# board.net
KiCad netlist of a schematic drawn in EAGLE
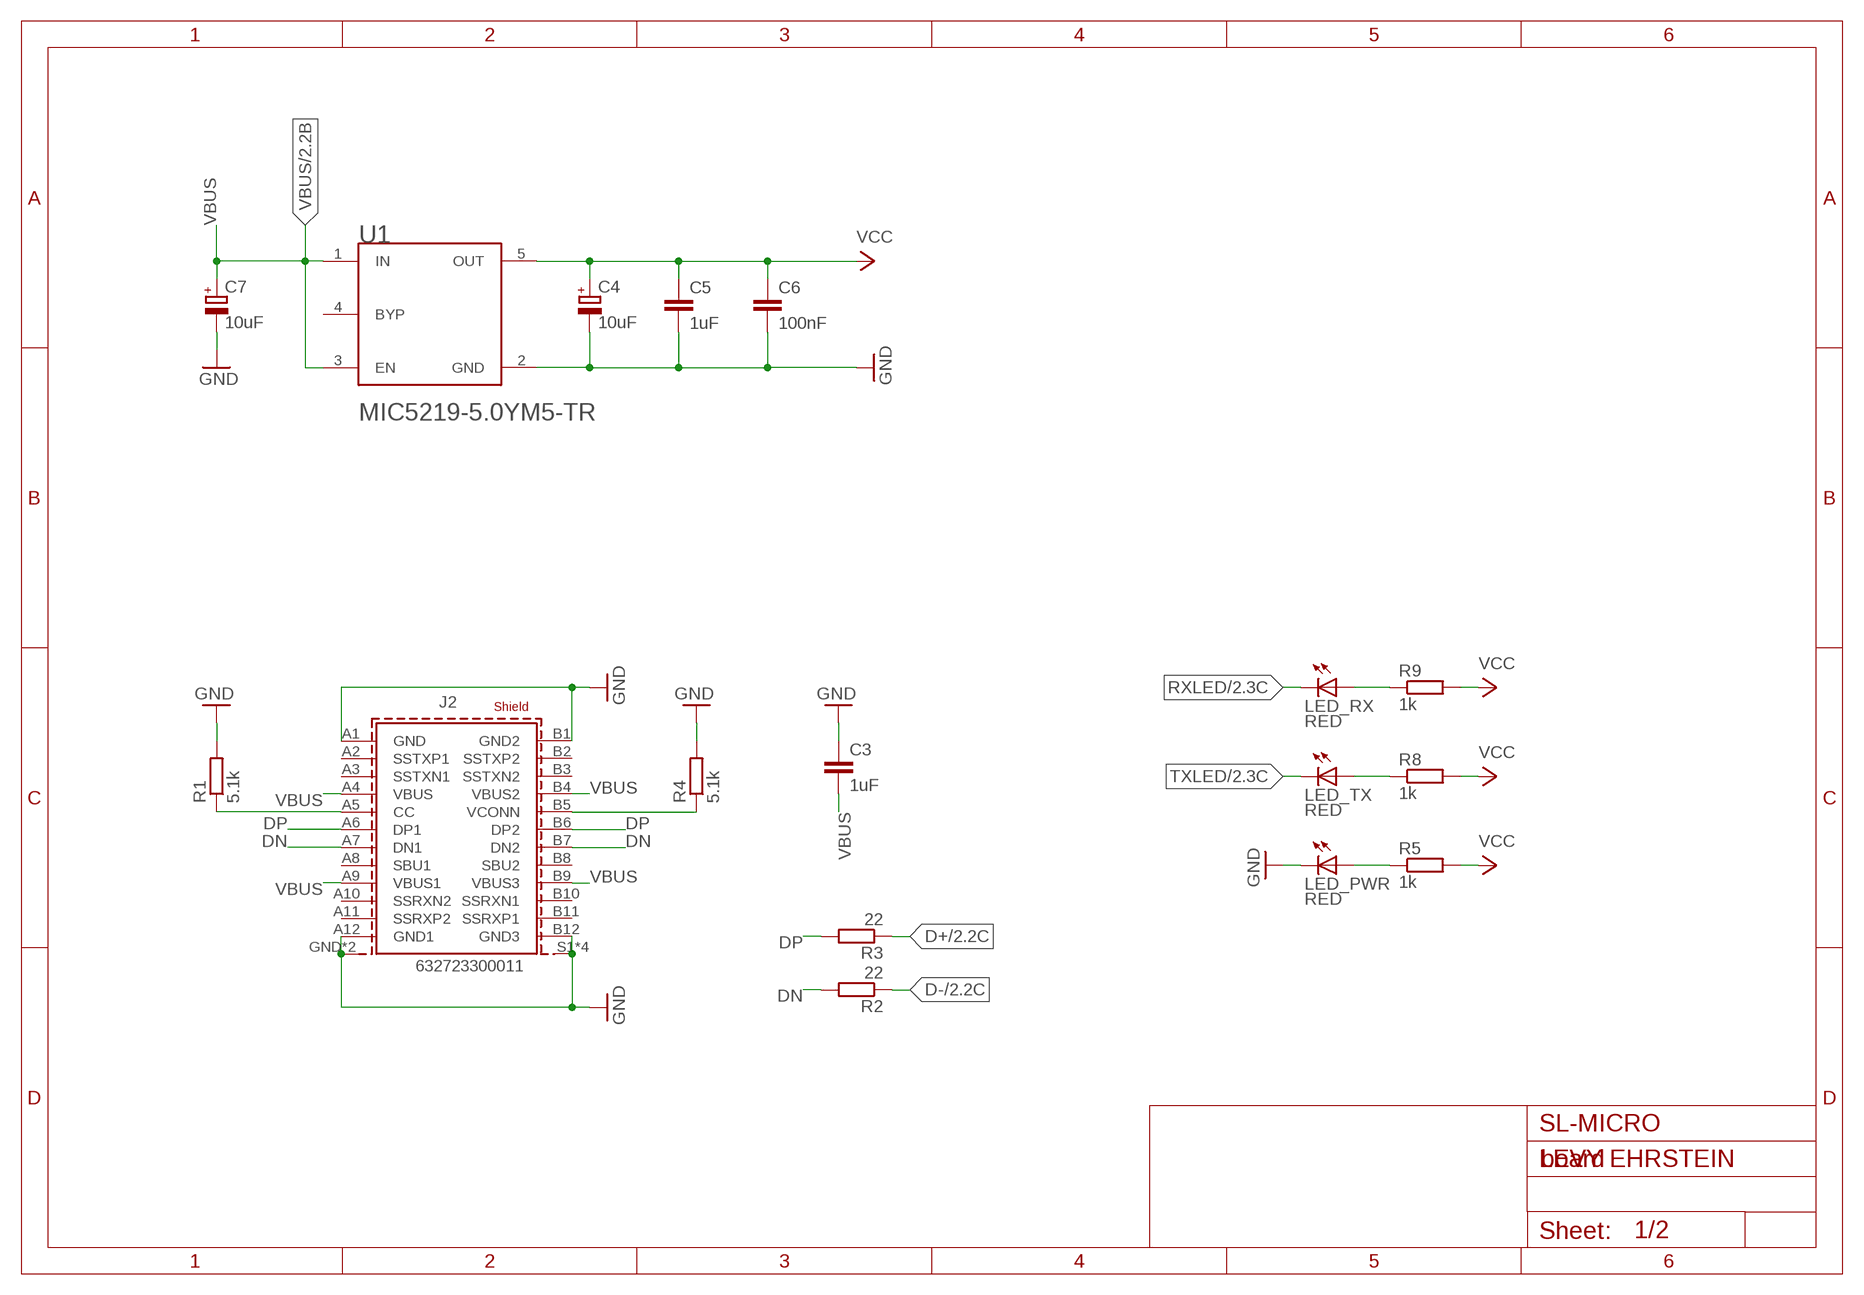
[diagram p0: schematic, sheet 1]
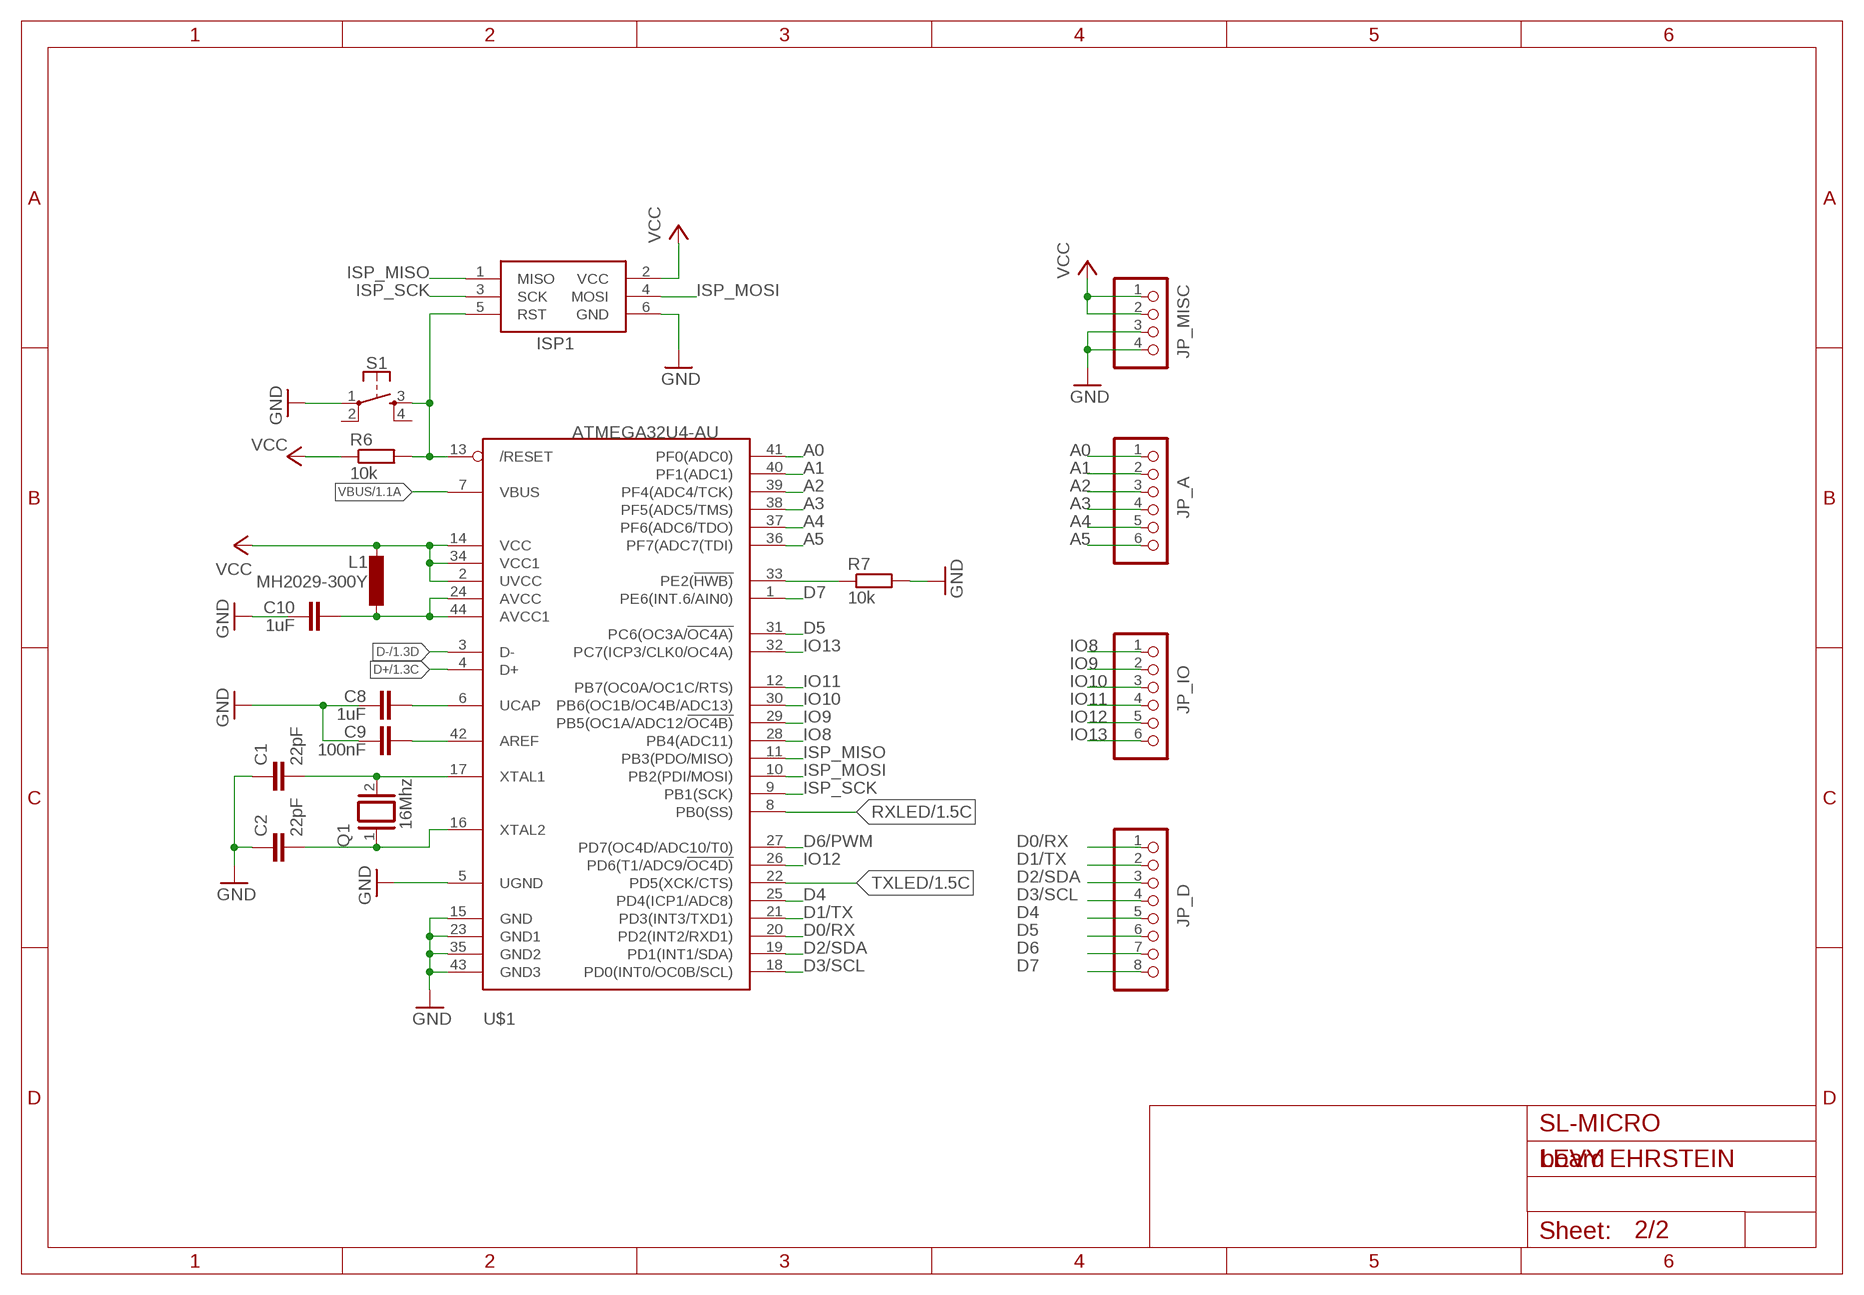
[diagram p1: schematic, sheet 2]

(export (version "E")
  (design (tool "Eeschema 10.0.6"))
  (components
    (comp (ref "C1")
      (value "22pF")
      (footprint "eagle-import:C0805")
      (libsource (lib "eagle-import") (part "C-EUC0805"))
    )
    (comp (ref "C2")
      (value "22pF")
      (footprint "eagle-import:C0805")
      (libsource (lib "eagle-import") (part "C-EUC0805"))
    )
    (comp (ref "C8")
      (value "1uF")
      (footprint "eagle-import:C0805")
      (libsource (lib "eagle-import") (part "C-EUC0805"))
    )
    (comp (ref "C9")
      (value "100nF")
      (footprint "eagle-import:C0805")
      (libsource (lib "eagle-import") (part "C-EUC0805"))
    )
    (comp (ref "C10")
      (value "1uF")
      (footprint "eagle-import:C0805")
      (libsource (lib "eagle-import") (part "C-EUC0805"))
    )
    (comp (ref "ISP1")
      (value "AVRISP-6")
      (footprint "eagle-import:AVRISP")
      (libsource (lib "eagle-import") (part "AVRISP-6"))
    )
    (comp (ref "JP_A")
      (value "PINHD-1X6")
      (footprint "eagle-import:1X06")
      (libsource (lib "eagle-import") (part "PINHD-1X6"))
    )
    (comp (ref "JP_D")
      (value "PINHD-1X8")
      (footprint "eagle-import:1X08")
      (libsource (lib "eagle-import") (part "PINHD-1X8"))
    )
    (comp (ref "JP_IO")
      (value "PINHD-1X6")
      (footprint "eagle-import:1X06")
      (libsource (lib "eagle-import") (part "PINHD-1X6"))
    )
    (comp (ref "JP_MISC")
      (value "PINHD-1X4")
      (footprint "eagle-import:1X04")
      (libsource (lib "eagle-import") (part "PINHD-1X4"))
    )
    (comp (ref "L1")
      (value "MH2029-300Y")
      (footprint "eagle-import:L2012C")
      (libsource (lib "eagle-import") (part "L-EUL2012C"))
    )
    (comp (ref "Q1")
      (value "16Mhz")
      (footprint "eagle-import:QS")
      (libsource (lib "eagle-import") (part "XTAL/S"))
    )
    (comp (ref "R6")
      (value "10k")
      (footprint "eagle-import:R0805")
      (libsource (lib "eagle-import") (part "R-EU_R0805"))
    )
    (comp (ref "R7")
      (value "10k")
      (footprint "eagle-import:R0805")
      (libsource (lib "eagle-import") (part "R-EU_R0805"))
    )
    (comp (ref "S1")
      (value "MOMENTARY-SWITCH-SPST-2-SMD-4.6X2.8MM")
      (footprint "eagle-import:TACTILE_SWITCH_SMD_4.6X2.8MM")
      (libsource (lib "eagle-import") (part "MOMENTARY-SWITCH-SPST-2-SMD-4.6X2.8MM"))
    )
    (comp (ref "U$1")
      (value "ATMEGA32U4-AU")
      (footprint "eagle-import:TQFP44")
      (libsource (lib "eagle-import") (part "ATMEGA32U4-AU"))
    )
    (comp (ref "C3")
      (value "1uF")
      (footprint "eagle-import:C0805")
      (libsource (lib "eagle-import") (part "C-EUC0805"))
    )
    (comp (ref "C4")
      (value "10uF")
      (footprint "eagle-import:SMC_B")
      (libsource (lib "eagle-import") (part "CPOL-EUSMCB"))
    )
    (comp (ref "C5")
      (value "1uF")
      (footprint "eagle-import:C0805")
      (libsource (lib "eagle-import") (part "C-EUC0805"))
    )
    (comp (ref "C6")
      (value "100nF")
      (footprint "eagle-import:C0805")
      (libsource (lib "eagle-import") (part "C-EUC0805"))
    )
    (comp (ref "C7")
      (value "10uF")
      (footprint "eagle-import:SMC_B")
      (libsource (lib "eagle-import") (part "CPOL-EUSMCB"))
    )
    (comp (ref "J2")
      (value "632723300011")
      (footprint "eagle-import:632723300011")
      (libsource (lib "eagle-import") (part "632723300011"))
    )
    (comp (ref "LED_PWR")
      (value "RED")
      (footprint "eagle-import:CHIP-LED0805")
      (libsource (lib "eagle-import") (part "LEDCHIP-LED0805"))
    )
    (comp (ref "LED_RX")
      (value "RED")
      (footprint "eagle-import:CHIP-LED0805")
      (libsource (lib "eagle-import") (part "LEDCHIP-LED0805"))
    )
    (comp (ref "LED_TX")
      (value "RED")
      (footprint "eagle-import:CHIP-LED0805")
      (libsource (lib "eagle-import") (part "LEDCHIP-LED0805"))
    )
    (comp (ref "R1")
      (value "5.1k")
      (footprint "eagle-import:R0805")
      (libsource (lib "eagle-import") (part "R-EU_R0805"))
    )
    (comp (ref "R2")
      (value "22")
      (footprint "eagle-import:R0805")
      (libsource (lib "eagle-import") (part "R-EU_R0805"))
    )
    (comp (ref "R3")
      (value "22")
      (footprint "eagle-import:R0805")
      (libsource (lib "eagle-import") (part "R-EU_R0805"))
    )
    (comp (ref "R4")
      (value "5.1k")
      (footprint "eagle-import:R0805")
      (libsource (lib "eagle-import") (part "R-EU_R0805"))
    )
    (comp (ref "R5")
      (value "1k")
      (footprint "eagle-import:R0805")
      (libsource (lib "eagle-import") (part "R-EU_R0805"))
    )
    (comp (ref "R8")
      (value "1k")
      (footprint "eagle-import:R0805")
      (libsource (lib "eagle-import") (part "R-EU_R0805"))
    )
    (comp (ref "R9")
      (value "1k")
      (footprint "eagle-import:R0805")
      (libsource (lib "eagle-import") (part "R-EU_R0805"))
    )
    (comp (ref "U1")
      (value "MICROCHIP_TECHNOLOGY_MIC5219-5_0YM5-TRMICROCHIP_TECHNOLOGY_MIC5219-5_0YM5-TR_0_0")
      (footprint "eagle-import:MICROCHIP_TECHNOLOGY_MIC5219-5_0YM5-TR_0")
      (fields
        (field (name "DIGIKEY_PART_NUMBER") "576-2770-1-ND")
        (field (name "MF") "Microchip Technology")
        (field (name "MOUSER_PART_NUMBER") "998-MIC5219-5.0YM5TR")
      )
      (libsource (lib "eagle-import") (part "MICROCHIP_TECHNOLOGY_MIC5219-5_0YM5-TRMICROCHIP_TECHNOLOGY_MIC5219-5_0YM5-TR_0_0"))
    )
  )
  (nets
    (net (code "1") (name "A0") (class "Default")
      (node (ref "JP_A") (pin "1") (pinfunction "1_1") (pintype "passive"))
      (node (ref "U$1") (pin "41") (pinfunction "PF0(ADC0)_41") (pintype "bidirectional"))
    )
    (net (code "2") (name "A1") (class "Default")
      (node (ref "JP_A") (pin "2") (pinfunction "2_2") (pintype "passive"))
      (node (ref "U$1") (pin "40") (pinfunction "PF1(ADC1)_40") (pintype "bidirectional"))
    )
    (net (code "3") (name "A2") (class "Default")
      (node (ref "JP_A") (pin "3") (pinfunction "3_3") (pintype "passive"))
      (node (ref "U$1") (pin "39") (pinfunction "PF4(ADC4/TCK)_39") (pintype "bidirectional"))
    )
    (net (code "4") (name "A3") (class "Default")
      (node (ref "JP_A") (pin "4") (pinfunction "4_4") (pintype "passive"))
      (node (ref "U$1") (pin "38") (pinfunction "PF5(ADC5/TMS)_38") (pintype "bidirectional"))
    )
    (net (code "5") (name "A4") (class "Default")
      (node (ref "JP_A") (pin "5") (pinfunction "5_5") (pintype "passive"))
      (node (ref "U$1") (pin "37") (pinfunction "PF6(ADC6/TDO)_37") (pintype "bidirectional"))
    )
    (net (code "6") (name "A5") (class "Default")
      (node (ref "JP_A") (pin "6") (pinfunction "6_6") (pintype "passive"))
      (node (ref "U$1") (pin "36") (pinfunction "PF7(ADC7(TDI)_36") (pintype "bidirectional"))
    )
    (net (code "7") (name "D+") (class "Default")
      (node (ref "R3") (pin "1") (pinfunction "1_1") (pintype "passive"))
      (node (ref "U$1") (pin "4") (pinfunction "D+_4") (pintype "bidirectional"))
    )
    (net (code "8") (name "D-") (class "Default")
      (node (ref "R2") (pin "1") (pinfunction "1_1") (pintype "passive"))
      (node (ref "U$1") (pin "3") (pinfunction "D-_3") (pintype "bidirectional"))
    )
    (net (code "9") (name "D0{slash}RX") (class "Default")
      (node (ref "JP_D") (pin "1") (pinfunction "1_1") (pintype "passive"))
      (node (ref "U$1") (pin "20") (pinfunction "PD2(INT2/RXD1)_20") (pintype "bidirectional"))
    )
    (net (code "10") (name "D1{slash}TX") (class "Default")
      (node (ref "JP_D") (pin "2") (pinfunction "2_2") (pintype "passive"))
      (node (ref "U$1") (pin "21") (pinfunction "PD3(INT3/TXD1)_21") (pintype "bidirectional"))
    )
    (net (code "11") (name "D2{slash}SDA") (class "Default")
      (node (ref "JP_D") (pin "3") (pinfunction "3_3") (pintype "passive"))
      (node (ref "U$1") (pin "19") (pinfunction "PD1(INT1/SDA)_19") (pintype "bidirectional"))
    )
    (net (code "12") (name "D3{slash}SCL") (class "Default")
      (node (ref "JP_D") (pin "4") (pinfunction "4_4") (pintype "passive"))
      (node (ref "U$1") (pin "18") (pinfunction "PD0(INT0/OC0B/SCL)_18") (pintype "bidirectional"))
    )
    (net (code "13") (name "D4") (class "Default")
      (node (ref "JP_D") (pin "5") (pinfunction "5_5") (pintype "passive"))
      (node (ref "U$1") (pin "25") (pinfunction "PD4(ICP1/ADC8)_25") (pintype "bidirectional"))
    )
    (net (code "14") (name "D5") (class "Default")
      (node (ref "JP_D") (pin "6") (pinfunction "6_6") (pintype "passive"))
      (node (ref "U$1") (pin "31") (pinfunction "PC6(OC3A/~{OC4A})_31") (pintype "bidirectional"))
    )
    (net (code "15") (name "D6") (class "Default")
      (node (ref "JP_D") (pin "7") (pinfunction "7_7") (pintype "passive"))
    )
    (net (code "16") (name "D6{slash}PWM") (class "Default")
      (node (ref "U$1") (pin "27") (pinfunction "PD7(OC4D/ADC10/T0)_27") (pintype "bidirectional"))
    )
    (net (code "17") (name "D7") (class "Default")
      (node (ref "JP_D") (pin "8") (pinfunction "8_8") (pintype "passive"))
      (node (ref "U$1") (pin "1") (pinfunction "PE6(INT.6/AIN0)_1") (pintype "bidirectional"))
    )
    (net (code "18") (name "DN") (class "Default")
      (node (ref "J2") (pin "A7") (pinfunction "DN1_A7") (pintype "bidirectional"))
      (node (ref "J2") (pin "B7") (pinfunction "DN2_B7") (pintype "bidirectional"))
      (node (ref "R2") (pin "2") (pinfunction "2_2") (pintype "passive"))
    )
    (net (code "19") (name "DP") (class "Default")
      (node (ref "J2") (pin "A6") (pinfunction "DP1_A6") (pintype "bidirectional"))
      (node (ref "J2") (pin "B6") (pinfunction "DP2_B6") (pintype "bidirectional"))
      (node (ref "R3") (pin "2") (pinfunction "2_2") (pintype "passive"))
    )
    (net (code "20") (name "GND") (class "Default")
      (node (ref "C1") (pin "1") (pinfunction "1_1") (pintype "passive"))
      (node (ref "C10") (pin "1") (pinfunction "1_1") (pintype "passive"))
      (node (ref "C2") (pin "1") (pinfunction "1_1") (pintype "passive"))
      (node (ref "C3") (pin "1") (pinfunction "1_1") (pintype "passive"))
      (node (ref "C4") (pin "-") (pinfunction "-_-") (pintype "passive"))
      (node (ref "C5") (pin "2") (pinfunction "2_2") (pintype "passive"))
      (node (ref "C6") (pin "2") (pinfunction "2_2") (pintype "passive"))
      (node (ref "C7") (pin "-") (pinfunction "-_-") (pintype "passive"))
      (node (ref "C8") (pin "1") (pinfunction "1_1") (pintype "passive"))
      (node (ref "C9") (pin "1") (pinfunction "1_1") (pintype "passive"))
      (node (ref "ISP1") (pin "6") (pinfunction "GND_6") (pintype "power_in"))
      (node (ref "J2") (pin "A1") (pinfunction "GND_A1") (pintype "bidirectional"))
      (node (ref "J2") (pin "A12") (pinfunction "GND1_A12") (pintype "bidirectional"))
      (node (ref "J2") (pin "B1") (pinfunction "GND2_B1") (pintype "bidirectional"))
      (node (ref "J2") (pin "B12") (pinfunction "GND3_B12") (pintype "bidirectional"))
      (node (ref "J2") (pin "GND") (pinfunction "SHIELD_GND") (pintype "bidirectional"))
      (node (ref "J2") (pin "GND1") (pinfunction "SHIELD_GND1") (pintype "bidirectional"))
      (node (ref "J2") (pin "S1") (pinfunction "SHIELD1_S1") (pintype "bidirectional"))
      (node (ref "J2") (pin "S2") (pinfunction "SHIELD1_S2") (pintype "bidirectional"))
      (node (ref "J2") (pin "S3") (pinfunction "SHIELD1_S3") (pintype "bidirectional"))
      (node (ref "J2") (pin "S4") (pinfunction "SHIELD1_S4") (pintype "bidirectional"))
      (node (ref "JP_MISC") (pin "3") (pinfunction "3_3") (pintype "passive"))
      (node (ref "JP_MISC") (pin "4") (pinfunction "4_4") (pintype "passive"))
      (node (ref "LED_PWR") (pin "C") (pinfunction "C_C") (pintype "passive"))
      (node (ref "R1") (pin "2") (pinfunction "2_2") (pintype "passive"))
      (node (ref "R4") (pin "2") (pinfunction "2_2") (pintype "passive"))
      (node (ref "R7") (pin "2") (pinfunction "2_2") (pintype "passive"))
      (node (ref "S1") (pin "1") (pinfunction "1_1") (pintype "passive"))
      (node (ref "U$1") (pin "15") (pinfunction "GND_15") (pintype "bidirectional"))
      (node (ref "U$1") (pin "23") (pinfunction "GND1_23") (pintype "bidirectional"))
      (node (ref "U$1") (pin "35") (pinfunction "GND2_35") (pintype "bidirectional"))
      (node (ref "U$1") (pin "43") (pinfunction "GND3_43") (pintype "bidirectional"))
      (node (ref "U$1") (pin "5") (pinfunction "UGND_5") (pintype "bidirectional"))
      (node (ref "U1") (pin "2") (pinfunction "GND_2") (pintype "power_in"))
    )
    (net (code "21") (name "IO8") (class "Default")
      (node (ref "JP_IO") (pin "1") (pinfunction "1_1") (pintype "passive"))
      (node (ref "U$1") (pin "28") (pinfunction "PB4(ADC11)_28") (pintype "bidirectional"))
    )
    (net (code "22") (name "IO9") (class "Default")
      (node (ref "JP_IO") (pin "2") (pinfunction "2_2") (pintype "passive"))
      (node (ref "U$1") (pin "29") (pinfunction "PB5(OC1A/ADC12/~{OC4B})_29") (pintype "bidirectional"))
    )
    (net (code "23") (name "IO10") (class "Default")
      (node (ref "JP_IO") (pin "3") (pinfunction "3_3") (pintype "passive"))
      (node (ref "U$1") (pin "30") (pinfunction "PB6(OC1B/OC4B/ADC13)_30") (pintype "bidirectional"))
    )
    (net (code "24") (name "IO11") (class "Default")
      (node (ref "JP_IO") (pin "4") (pinfunction "4_4") (pintype "passive"))
      (node (ref "U$1") (pin "12") (pinfunction "PB7(OC0A/OC1C/RTS)_12") (pintype "bidirectional"))
    )
    (net (code "25") (name "IO12") (class "Default")
      (node (ref "JP_IO") (pin "5") (pinfunction "5_5") (pintype "passive"))
      (node (ref "U$1") (pin "26") (pinfunction "PD6(T1/ADC9/~{OC4D})_26") (pintype "bidirectional"))
    )
    (net (code "26") (name "IO13") (class "Default")
      (node (ref "JP_IO") (pin "6") (pinfunction "6_6") (pintype "passive"))
      (node (ref "U$1") (pin "32") (pinfunction "PC7(ICP3/CLK0/OC4A)_32") (pintype "bidirectional"))
    )
    (net (code "27") (name "ISP_MISO") (class "Default")
      (node (ref "ISP1") (pin "1") (pinfunction "MISO_1") (pintype "input"))
      (node (ref "U$1") (pin "11") (pinfunction "PB3(PDO/MISO)_11") (pintype "bidirectional"))
    )
    (net (code "28") (name "ISP_MOSI") (class "Default")
      (node (ref "ISP1") (pin "4") (pinfunction "MOSI_4") (pintype "output"))
      (node (ref "U$1") (pin "10") (pinfunction "PB2(PDI/MOSI)_10") (pintype "bidirectional"))
    )
    (net (code "29") (name "ISP_SCK") (class "Default")
      (node (ref "ISP1") (pin "3") (pinfunction "SCK_3") (pintype "output"))
      (node (ref "U$1") (pin "9") (pinfunction "PB1(SCK)_9") (pintype "bidirectional"))
    )
    (net (code "30") (name "Net-(ISP1-RST)") (class "Default")
      (node (ref "ISP1") (pin "5") (pinfunction "RST_5") (pintype "output"))
      (node (ref "R6") (pin "2") (pinfunction "2_2") (pintype "passive"))
      (node (ref "S1") (pin "3") (pinfunction "3_3") (pintype "passive"))
      (node (ref "U$1") (pin "13") (pinfunction "/RESET_13") (pintype "bidirectional"))
    )
    (net (code "31") (name "Net-(J2-CC)") (class "Default")
      (node (ref "J2") (pin "A5") (pinfunction "CC_A5") (pintype "bidirectional"))
      (node (ref "R1") (pin "1") (pinfunction "1_1") (pintype "passive"))
    )
    (net (code "32") (name "Net-(J2-VCONN)") (class "Default")
      (node (ref "J2") (pin "B5") (pinfunction "VCONN_B5") (pintype "bidirectional"))
      (node (ref "R4") (pin "1") (pinfunction "1_1") (pintype "passive"))
    )
    (net (code "33") (name "Net-(LED_PWR-PadA)") (class "Default")
      (node (ref "LED_PWR") (pin "A") (pinfunction "A_A") (pintype "passive"))
      (node (ref "R5") (pin "1") (pinfunction "1_1") (pintype "passive"))
    )
    (net (code "34") (name "Net-(LED_RX-PadA)") (class "Default")
      (node (ref "LED_RX") (pin "A") (pinfunction "A_A") (pintype "passive"))
      (node (ref "R9") (pin "1") (pinfunction "1_1") (pintype "passive"))
    )
    (net (code "35") (name "Net-(LED_TX-PadA)") (class "Default")
      (node (ref "LED_TX") (pin "A") (pinfunction "A_A") (pintype "passive"))
      (node (ref "R8") (pin "1") (pinfunction "1_1") (pintype "passive"))
    )
    (net (code "36") (name "Net-(U$1-AREF)") (class "Default")
      (node (ref "C9") (pin "2") (pinfunction "2_2") (pintype "passive"))
      (node (ref "U$1") (pin "42") (pinfunction "AREF_42") (pintype "bidirectional"))
    )
    (net (code "37") (name "Net-(U$1-AVCC)") (class "Default")
      (node (ref "C10") (pin "2") (pinfunction "2_2") (pintype "passive"))
      (node (ref "L1") (pin "1") (pinfunction "1_1") (pintype "passive"))
      (node (ref "U$1") (pin "24") (pinfunction "AVCC_24") (pintype "bidirectional"))
      (node (ref "U$1") (pin "44") (pinfunction "AVCC1_44") (pintype "bidirectional"))
    )
    (net (code "38") (name "Net-(U$1-PE2(~{HWB}))") (class "Default")
      (node (ref "R7") (pin "1") (pinfunction "1_1") (pintype "passive"))
      (node (ref "U$1") (pin "33") (pinfunction "PE2(~{HWB})_33") (pintype "bidirectional"))
    )
    (net (code "39") (name "Net-(U$1-UCAP)") (class "Default")
      (node (ref "C8") (pin "2") (pinfunction "2_2") (pintype "passive"))
      (node (ref "U$1") (pin "6") (pinfunction "UCAP_6") (pintype "bidirectional"))
    )
    (net (code "40") (name "Net-(U$1-XTAL1)") (class "Default")
      (node (ref "C1") (pin "2") (pinfunction "2_2") (pintype "passive"))
      (node (ref "Q1") (pin "2") (pinfunction "2_2") (pintype "passive"))
      (node (ref "U$1") (pin "17") (pinfunction "XTAL1_17") (pintype "bidirectional"))
    )
    (net (code "41") (name "Net-(U$1-XTAL2)") (class "Default")
      (node (ref "C2") (pin "2") (pinfunction "2_2") (pintype "passive"))
      (node (ref "Q1") (pin "1") (pinfunction "1_1") (pintype "passive"))
      (node (ref "U$1") (pin "16") (pinfunction "XTAL2_16") (pintype "bidirectional"))
    )
    (net (code "42") (name "RXLED") (class "Default")
      (node (ref "LED_RX") (pin "C") (pinfunction "C_C") (pintype "passive"))
      (node (ref "U$1") (pin "8") (pinfunction "PB0(SS)_8") (pintype "bidirectional"))
    )
    (net (code "43") (name "TXLED") (class "Default")
      (node (ref "LED_TX") (pin "C") (pinfunction "C_C") (pintype "passive"))
      (node (ref "U$1") (pin "22") (pinfunction "PD5(XCK/CTS)_22") (pintype "bidirectional"))
    )
    (net (code "44") (name "VBUS") (class "Default")
      (node (ref "C3") (pin "2") (pinfunction "2_2") (pintype "passive"))
      (node (ref "C7") (pin "+") (pinfunction "+_+") (pintype "passive"))
      (node (ref "J2") (pin "A4") (pinfunction "VBUS_A4") (pintype "bidirectional"))
      (node (ref "J2") (pin "A9") (pinfunction "VBUS1_A9") (pintype "bidirectional"))
      (node (ref "J2") (pin "B4") (pinfunction "VBUS2_B4") (pintype "bidirectional"))
      (node (ref "J2") (pin "B9") (pinfunction "VBUS3_B9") (pintype "bidirectional"))
      (node (ref "U$1") (pin "7") (pinfunction "VBUS_7") (pintype "bidirectional"))
      (node (ref "U1") (pin "1") (pinfunction "IN_1") (pintype "power_in"))
      (node (ref "U1") (pin "3") (pinfunction "EN_3") (pintype "input"))
    )
    (net (code "45") (name "VCC") (class "Default")
      (node (ref "C4") (pin "+") (pinfunction "+_+") (pintype "passive"))
      (node (ref "C5") (pin "1") (pinfunction "1_1") (pintype "passive"))
      (node (ref "C6") (pin "1") (pinfunction "1_1") (pintype "passive"))
      (node (ref "ISP1") (pin "2") (pinfunction "VCC_2") (pintype "power_in"))
      (node (ref "JP_MISC") (pin "1") (pinfunction "1_1") (pintype "passive"))
      (node (ref "JP_MISC") (pin "2") (pinfunction "2_2") (pintype "passive"))
      (node (ref "L1") (pin "2") (pinfunction "2_2") (pintype "passive"))
      (node (ref "R5") (pin "2") (pinfunction "2_2") (pintype "passive"))
      (node (ref "R6") (pin "1") (pinfunction "1_1") (pintype "passive"))
      (node (ref "R8") (pin "2") (pinfunction "2_2") (pintype "passive"))
      (node (ref "R9") (pin "2") (pinfunction "2_2") (pintype "passive"))
      (node (ref "U$1") (pin "14") (pinfunction "VCC_14") (pintype "bidirectional"))
      (node (ref "U$1") (pin "2") (pinfunction "UVCC_2") (pintype "bidirectional"))
      (node (ref "U$1") (pin "34") (pinfunction "VCC1_34") (pintype "bidirectional"))
      (node (ref "U1") (pin "5") (pinfunction "OUT_5") (pintype "power_in"))
    )
    (net (code "46") (name "unconnected-(J2-SBU1-PadA8)") (class "Default")
      (node (ref "J2") (pin "A8") (pinfunction "SBU1_A8") (pintype "bidirectional"))
    )
    (net (code "47") (name "unconnected-(J2-SBU2-PadB8)") (class "Default")
      (node (ref "J2") (pin "B8") (pinfunction "SBU2_B8") (pintype "bidirectional"))
    )
    (net (code "48") (name "unconnected-(J2-SSRXN1-PadB10)") (class "Default")
      (node (ref "J2") (pin "B10") (pinfunction "SSRXN1_B10") (pintype "bidirectional"))
    )
    (net (code "49") (name "unconnected-(J2-SSRXN2-PadA10)") (class "Default")
      (node (ref "J2") (pin "A10") (pinfunction "SSRXN2_A10") (pintype "bidirectional"))
    )
    (net (code "50") (name "unconnected-(J2-SSRXP1-PadB11)") (class "Default")
      (node (ref "J2") (pin "B11") (pinfunction "SSRXP1_B11") (pintype "bidirectional"))
    )
    (net (code "51") (name "unconnected-(J2-SSRXP2-PadA11)") (class "Default")
      (node (ref "J2") (pin "A11") (pinfunction "SSRXP2_A11") (pintype "bidirectional"))
    )
    (net (code "52") (name "unconnected-(J2-SSTXN1-PadA3)") (class "Default")
      (node (ref "J2") (pin "A3") (pinfunction "SSTXN1_A3") (pintype "bidirectional"))
    )
    (net (code "53") (name "unconnected-(J2-SSTXN2-PadB3)") (class "Default")
      (node (ref "J2") (pin "B3") (pinfunction "SSTXN2_B3") (pintype "bidirectional"))
    )
    (net (code "54") (name "unconnected-(J2-SSTXP1-PadA2)") (class "Default")
      (node (ref "J2") (pin "A2") (pinfunction "SSTXP1_A2") (pintype "bidirectional"))
    )
    (net (code "55") (name "unconnected-(J2-SSTXP2-PadB2)") (class "Default")
      (node (ref "J2") (pin "B2") (pinfunction "SSTXP2_B2") (pintype "bidirectional"))
    )
    (net (code "56") (name "unconnected-(S1-Pad2)") (class "Default")
      (node (ref "S1") (pin "2") (pinfunction "2_2") (pintype "passive"))
    )
    (net (code "57") (name "unconnected-(S1-Pad4)") (class "Default")
      (node (ref "S1") (pin "4") (pinfunction "4_4") (pintype "passive"))
    )
    (net (code "58") (name "unconnected-(U1-BYP-Pad4)") (class "Default")
      (node (ref "U1") (pin "4") (pinfunction "BYP_4") (pintype "passive"))
    )
  )
)
